# motor_DRV.net
KiCad netlist of a schematic drawn in Altium Designer
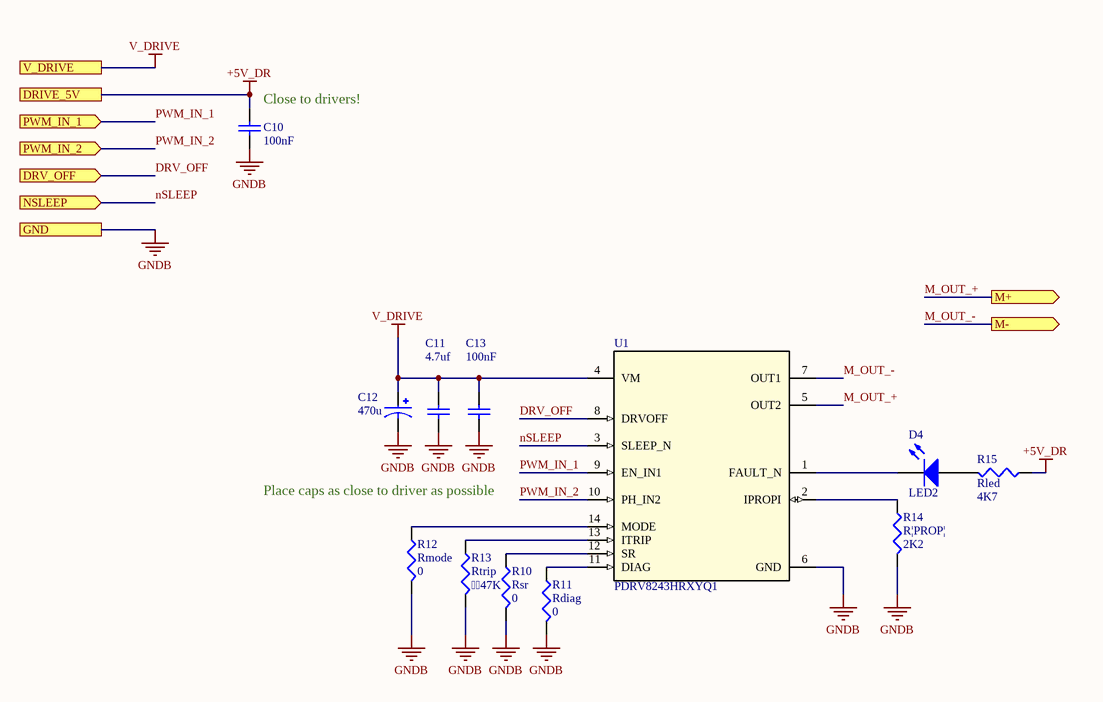
[diagram p0: motor_DRV.SchDoc]

(export (version "E")
  (design (tool "Eeschema 10.0.6"))
  (components
    (comp (ref "C10")
      (value "100nF")
      (footprint "1608[0603]")
      (description "Capacitor (Semiconductor SIM Model)")
      (fields (field (name "Comment") "Cap Semi") (field (name "PUBLISHER") "Altium Limited"))
      (libsource (lib "Miscellaneous Devices") (part "Cap Semi"))
    )
    (comp (ref "C11")
      (value "4.7uf")
      (footprint "1608[0603]")
      (description "Capacitor (Semiconductor SIM Model)")
      (fields (field (name "Comment") "Cap Semi") (field (name "PUBLISHER") "Altium Limited"))
      (libsource (lib "Miscellaneous Devices") (part "Cap Semi"))
    )
    (comp (ref "C12")
      (value "470u")
      (footprint "CAPPRD500W60D800H1500")
      (description "470F 25V Aluminum Electrolytic Capacitors Radial, Can 8000 Hrs @ 105C")
      (fields (field (name "MF") "Panasonic") (field (name "MP") "EEUFR1E471YB"))
      (libsource (lib "pana25v470u") (part "EEUFR1E471YB"))
    )
    (comp (ref "C13")
      (value "100nF")
      (footprint "1608[0603]")
      (description "Capacitor (Semiconductor SIM Model)")
      (fields (field (name "Comment") "Cap Semi") (field (name "PUBLISHER") "Altium Limited"))
      (libsource (lib "Miscellaneous Devices") (part "Cap Semi"))
    )
    (comp (ref "D4")
      (value "LED2")
      (footprint "1608[0603]")
      (description "Typical RED, GREEN, YELLOW, AMBER GaAs LED")
      (fields (field (name "PUBLISHER") "Altium Limited"))
      (libsource (lib "Miscellaneous Devices") (part "LED2"))
    )
    (comp (ref "R10")
      (value "Rsr")
      (footprint "J1-0603")
      (description "Resistor")
      (fields (field (name "ALTIUM_VALUE") "0") (field (name "PUBLISHER") "Altium Limited"))
      (libsource (lib "Miscellaneous Devices") (part "Res3"))
    )
    (comp (ref "R11")
      (value "Rdiag")
      (footprint "J1-0603")
      (description "Resistor")
      (fields (field (name "ALTIUM_VALUE") "0") (field (name "PUBLISHER") "Altium Limited"))
      (libsource (lib "Miscellaneous Devices") (part "Res3"))
    )
    (comp (ref "R12")
      (value "Rmode")
      (footprint "J1-0603")
      (description "Resistor")
      (fields (field (name "ALTIUM_VALUE") "0") (field (name "PUBLISHER") "Altium Limited"))
      (libsource (lib "Miscellaneous Devices") (part "Res3"))
    )
    (comp (ref "R13")
      (value "Rtrip")
      (footprint "J1-0603")
      (description "Resistor")
      (fields (field (name "ALTIUM_VALUE") "47K") (field (name "PUBLISHER") "Altium Limited"))
      (libsource (lib "Miscellaneous Devices") (part "Res3"))
    )
    (comp (ref "R14")
      (value "R¦PROP¦")
      (footprint "J1-0603")
      (description "Resistor")
      (fields (field (name "ALTIUM_VALUE") "2K2") (field (name "PUBLISHER") "Altium Limited"))
      (libsource (lib "Miscellaneous Devices") (part "Res3"))
    )
    (comp (ref "R15")
      (value "Rled")
      (footprint "J1-0603")
      (description "Resistor")
      (fields (field (name "ALTIUM_VALUE") "4K7") (field (name "PUBLISHER") "Altium Limited"))
      (libsource (lib "Miscellaneous Devices") (part "Res3"))
    )
    (comp (ref "U1")
      (value "PDRV8243HRXYQ1")
      (footprint "RXY0014A-MFG")
      (description "No Description Available")
      (fields (field (name "COPYRIGHT") "Copyright (C) 2021 Ultra Librarian. All rights reserved."))
      (libsource (lib "PDRV8243HRXYQ1") (part "PDRV8243HRXYQ1"))
    )
  )
  (nets
    (net (code "1") (name "+5V_DR") (class "Default")
      (node (ref "C10") (pin "2") (pinfunction "2_2") (pintype "passive"))
      (node (ref "R15") (pin "2") (pinfunction "2_2") (pintype "passive"))
    )
    (net (code "2") (name "/DRV_OFF") (class "Default")
      (node (ref "U1") (pin "8") (pinfunction "DRVOFF_8") (pintype "input"))
    )
    (net (code "3") (name "/M_OUT_+") (class "Default")
      (node (ref "U1") (pin "5") (pinfunction "OUT2_5") (pintype "passive"))
    )
    (net (code "4") (name "/M_OUT_-") (class "Default")
      (node (ref "U1") (pin "7") (pinfunction "OUT1_7") (pintype "passive"))
    )
    (net (code "5") (name "/PWM_IN_1") (class "Default")
      (node (ref "U1") (pin "9") (pinfunction "EN_IN1_9") (pintype "input"))
    )
    (net (code "6") (name "/PWM_IN_2") (class "Default")
      (node (ref "U1") (pin "10") (pinfunction "PH_IN2_10") (pintype "input"))
    )
    (net (code "7") (name "/nSLEEP") (class "Default")
      (node (ref "U1") (pin "3") (pinfunction "SLEEP_N_3") (pintype "input"))
    )
    (net (code "8") (name "GNDB") (class "Default")
      (node (ref "C10") (pin "1") (pinfunction "1_1") (pintype "passive"))
      (node (ref "C11") (pin "1") (pinfunction "1_1") (pintype "passive"))
      (node (ref "C12") (pin "N") (pinfunction "N_N") (pintype "passive"))
      (node (ref "C13") (pin "1") (pinfunction "1_1") (pintype "passive"))
      (node (ref "R10") (pin "2") (pinfunction "2_2") (pintype "passive"))
      (node (ref "R11") (pin "2") (pinfunction "2_2") (pintype "passive"))
      (node (ref "R12") (pin "2") (pinfunction "2_2") (pintype "passive"))
      (node (ref "R13") (pin "2") (pinfunction "2_2") (pintype "passive"))
      (node (ref "R14") (pin "2") (pinfunction "2_2") (pintype "passive"))
      (node (ref "U1") (pin "6") (pinfunction "GND_6") (pintype "power_in"))
    )
    (net (code "9") (name "Net-(D4-A)") (class "Default")
      (node (ref "D4") (pin "1") (pinfunction "A_1") (pintype "passive"))
      (node (ref "R15") (pin "1") (pinfunction "1_1") (pintype "passive"))
    )
    (net (code "10") (name "Net-(D4-K)") (class "Default")
      (node (ref "D4") (pin "2") (pinfunction "K_2") (pintype "passive"))
      (node (ref "U1") (pin "1") (pinfunction "FAULT_N_1") (pintype "open_collector"))
    )
    (net (code "11") (name "Net-(U1-DIAG)") (class "Default")
      (node (ref "R11") (pin "1") (pinfunction "1_1") (pintype "passive"))
      (node (ref "U1") (pin "11") (pinfunction "DIAG_11") (pintype "input"))
    )
    (net (code "12") (name "Net-(U1-IPROPI)") (class "Default")
      (node (ref "R14") (pin "1") (pinfunction "1_1") (pintype "passive"))
      (node (ref "U1") (pin "2") (pinfunction "IPROPI_2") (pintype "bidirectional"))
    )
    (net (code "13") (name "Net-(U1-ITRIP)") (class "Default")
      (node (ref "R13") (pin "1") (pinfunction "1_1") (pintype "passive"))
      (node (ref "U1") (pin "13") (pinfunction "ITRIP_13") (pintype "input"))
    )
    (net (code "14") (name "Net-(U1-MODE)") (class "Default")
      (node (ref "R12") (pin "1") (pinfunction "1_1") (pintype "passive"))
      (node (ref "U1") (pin "14") (pinfunction "MODE_14") (pintype "input"))
    )
    (net (code "15") (name "Net-(U1-SR)") (class "Default")
      (node (ref "R10") (pin "1") (pinfunction "1_1") (pintype "passive"))
      (node (ref "U1") (pin "12") (pinfunction "SR_12") (pintype "input"))
    )
    (net (code "16") (name "V_DRIVE") (class "Default")
      (node (ref "C11") (pin "2") (pinfunction "2_2") (pintype "passive"))
      (node (ref "C12") (pin "P") (pinfunction "P_P") (pintype "passive"))
      (node (ref "C13") (pin "2") (pinfunction "2_2") (pintype "passive"))
      (node (ref "U1") (pin "4") (pinfunction "VM_4") (pintype "power_in"))
    )
  )
)
